# dual_supply.net
KiCad netlist of a schematic drawn in EAGLE
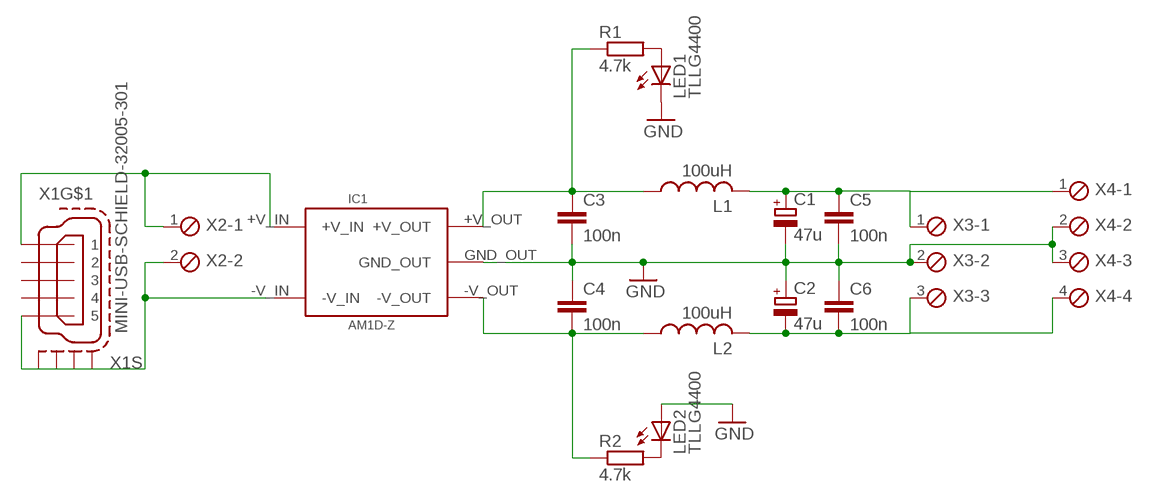
[diagram p0: schematic, sheet 1]

(export (version "E")
  (design (tool "Eeschema 10.0.6"))
  (components
    (comp (ref "C1")
      (value "47u")
      (footprint "eagle-import:E3,5-8")
      (libsource (lib "eagle-import") (part "CPOL-EUE3.5-8"))
    )
    (comp (ref "C2")
      (value "47u")
      (footprint "eagle-import:E3,5-8")
      (libsource (lib "eagle-import") (part "CPOL-EUE3.5-8"))
    )
    (comp (ref "C3")
      (value "100n")
      (footprint "eagle-import:C0805")
      (libsource (lib "eagle-import") (part "C-EUC0805"))
    )
    (comp (ref "C4")
      (value "100n")
      (footprint "eagle-import:C0805")
      (libsource (lib "eagle-import") (part "C-EUC0805"))
    )
    (comp (ref "C5")
      (value "100n")
      (footprint "eagle-import:C0805")
      (libsource (lib "eagle-import") (part "C-EUC0805"))
    )
    (comp (ref "C6")
      (value "100n")
      (footprint "eagle-import:C0805")
      (libsource (lib "eagle-import") (part "C-EUC0805"))
    )
    (comp (ref "IC1")
      (value "AM1D-Z")
      (footprint "eagle-import:AM1D-Z")
      (libsource (lib "eagle-import") (part "AM1D-Z"))
    )
    (comp (ref "L1")
      (value "100uH")
      (footprint "eagle-import:IR-2")
      (libsource (lib "eagle-import") (part "L-USIR-2"))
    )
    (comp (ref "L2")
      (value "100uH")
      (footprint "eagle-import:IR-2")
      (libsource (lib "eagle-import") (part "L-USIR-2"))
    )
    (comp (ref "LED1")
      (value "TLLG4400")
      (footprint "eagle-import:LED3MM")
      (fields (field (name "MF") "VISHAY SEMICONDUCTOR"))
      (libsource (lib "eagle-import") (part "TLLG4400"))
    )
    (comp (ref "LED2")
      (value "TLLG4400")
      (footprint "eagle-import:LED3MM")
      (fields (field (name "MF") "VISHAY SEMICONDUCTOR"))
      (libsource (lib "eagle-import") (part "TLLG4400"))
    )
    (comp (ref "R1")
      (value "4.7k")
      (footprint "eagle-import:R0805")
      (libsource (lib "eagle-import") (part "R-EU_R0805"))
    )
    (comp (ref "R2")
      (value "4.7k")
      (footprint "eagle-import:R0805")
      (libsource (lib "eagle-import") (part "R-EU_R0805"))
    )
    (comp (ref "X1")
      (value "MINI-USB-SCHIELD-32005-301")
      (footprint "eagle-import:32005-301")
      (libsource (lib "eagle-import") (part "MINI-USB-SCHIELD-32005-301"))
    )
    (comp (ref "X2")
      (value "MPT2")
      (footprint "eagle-import:2POL254")
      (libsource (lib "eagle-import") (part "MPT2"))
    )
    (comp (ref "X3")
      (value "MPT3")
      (footprint "eagle-import:3POL254")
      (libsource (lib "eagle-import") (part "MPT3"))
    )
    (comp (ref "X4")
      (value "MPT4")
      (footprint "eagle-import:4POL254")
      (libsource (lib "eagle-import") (part "MPT4"))
    )
  )
  (nets
    (net (code "1") (name "GND") (class "Default")
      (node (ref "C1") (pin "-") (pinfunction "-_-") (pintype "passive"))
      (node (ref "C2") (pin "+") (pinfunction "+_+") (pintype "passive"))
      (node (ref "C3") (pin "2") (pinfunction "2_2") (pintype "passive"))
      (node (ref "C4") (pin "1") (pinfunction "1_1") (pintype "passive"))
      (node (ref "C5") (pin "2") (pinfunction "2_2") (pintype "passive"))
      (node (ref "C6") (pin "1") (pinfunction "1_1") (pintype "passive"))
      (node (ref "IC1") (pin "GND_OUT") (pinfunction "GND_OUT_GND_OUT") (pintype "bidirectional"))
      (node (ref "LED1") (pin "K") (pinfunction "C_K") (pintype "passive"))
      (node (ref "LED2") (pin "A") (pinfunction "A_A") (pintype "passive"))
      (node (ref "X3") (pin "2") (pinfunction "1_2") (pintype "passive"))
      (node (ref "X4") (pin "2") (pinfunction "1_2") (pintype "passive"))
      (node (ref "X4") (pin "3") (pinfunction "1_3") (pintype "passive"))
    )
    (net (code "2") (name "Net-(C1-Pad+)") (class "Default")
      (node (ref "C1") (pin "+") (pinfunction "+_+") (pintype "passive"))
      (node (ref "C5") (pin "1") (pinfunction "1_1") (pintype "passive"))
      (node (ref "L1") (pin "2") (pinfunction "2_2") (pintype "passive"))
      (node (ref "X3") (pin "1") (pinfunction "1_1") (pintype "passive"))
      (node (ref "X4") (pin "1") (pinfunction "1_1") (pintype "passive"))
    )
    (net (code "3") (name "Net-(C3-Pad1)") (class "Default")
      (node (ref "C3") (pin "1") (pinfunction "1_1") (pintype "passive"))
      (node (ref "IC1") (pin "+V_OUT") (pinfunction "+V_OUT_+V_OUT") (pintype "bidirectional"))
      (node (ref "L1") (pin "1") (pinfunction "1_1") (pintype "passive"))
      (node (ref "R1") (pin "1") (pinfunction "1_1") (pintype "passive"))
    )
    (net (code "4") (name "Net-(C4-Pad2)") (class "Default")
      (node (ref "C4") (pin "2") (pinfunction "2_2") (pintype "passive"))
      (node (ref "IC1") (pin "-V_OUT") (pinfunction "-V_OUT_-V_OUT") (pintype "bidirectional"))
      (node (ref "L2") (pin "1") (pinfunction "1_1") (pintype "passive"))
      (node (ref "R2") (pin "1") (pinfunction "1_1") (pintype "passive"))
    )
    (net (code "5") (name "Net-(IC1-Pad+V_IN)") (class "Default")
      (node (ref "IC1") (pin "+V_IN") (pinfunction "+V_IN_+V_IN") (pintype "bidirectional"))
      (node (ref "X1") (pin "1") (pinfunction "1_1") (pintype "passive"))
      (node (ref "X2") (pin "1") (pinfunction "1_1") (pintype "passive"))
    )
    (net (code "6") (name "Net-(LED1-PadA)") (class "Default")
      (node (ref "LED1") (pin "A") (pinfunction "A_A") (pintype "passive"))
      (node (ref "R1") (pin "2") (pinfunction "2_2") (pintype "passive"))
    )
    (net (code "7") (name "Net-(LED2-C)") (class "Default")
      (node (ref "LED2") (pin "K") (pinfunction "C_K") (pintype "passive"))
      (node (ref "R2") (pin "2") (pinfunction "2_2") (pintype "passive"))
    )
    (net (code "8") (name "Net-(X1B-S1)") (class "Default")
      (node (ref "IC1") (pin "-V_IN") (pinfunction "-V_IN_-V_IN") (pintype "bidirectional"))
      (node (ref "X1") (pin "5") (pinfunction "5_5") (pintype "passive"))
      (node (ref "X1") (pin "M1") (pinfunction "S1_M1") (pintype "passive"))
      (node (ref "X1") (pin "M2") (pinfunction "S2_M2") (pintype "passive"))
      (node (ref "X1") (pin "M3") (pinfunction "S3_M3") (pintype "passive"))
      (node (ref "X1") (pin "M4") (pinfunction "S4_M4") (pintype "passive"))
      (node (ref "X2") (pin "2") (pinfunction "1_2") (pintype "passive"))
    )
    (net (code "9") (name "Net-(X3C-1)") (class "Default")
      (node (ref "C2") (pin "-") (pinfunction "-_-") (pintype "passive"))
      (node (ref "C6") (pin "2") (pinfunction "2_2") (pintype "passive"))
      (node (ref "L2") (pin "2") (pinfunction "2_2") (pintype "passive"))
      (node (ref "X3") (pin "3") (pinfunction "1_3") (pintype "passive"))
      (node (ref "X4") (pin "4") (pinfunction "1_4") (pintype "passive"))
    )
    (net (code "10") (name "unconnected-(X1-Pad2)") (class "Default")
      (node (ref "X1") (pin "2") (pinfunction "2_2") (pintype "passive"))
    )
    (net (code "11") (name "unconnected-(X1-Pad3)") (class "Default")
      (node (ref "X1") (pin "3") (pinfunction "3_3") (pintype "passive"))
    )
    (net (code "12") (name "unconnected-(X1-Pad4)") (class "Default")
      (node (ref "X1") (pin "4") (pinfunction "4_4") (pintype "passive"))
    )
  )
)
